# V1_1.net
KiCad netlist of a schematic drawn in Altium Designer
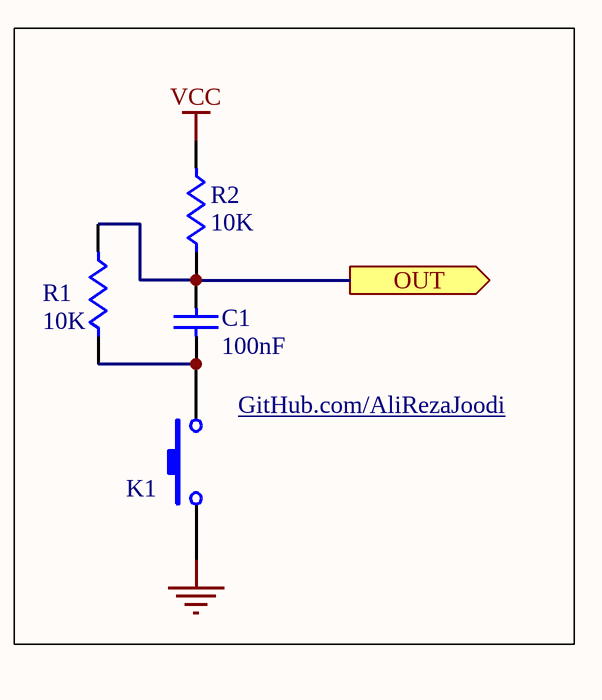
[diagram p0: V1.1.SchDoc]

(export (version "E")
  (design (tool "Eeschema 10.0.6"))
  (components
    (comp (ref "C1")
      (value "100nF")
      (footprint "CAPNTO2.54-3.56x2.03")
      (description "Capacitor")
      (fields (field (name "MANUFACTURER") "Generic Components") (field (name "PUBLISHER") "Altium Limited"))
      (libsource (lib "Miscellaneous Devices") (part "Cap"))
    )
    (comp (ref "K1")
      (value "SW-PB")
      (footprint "SPST-2_2")
      (description "Switch")
      (fields (field (name "MANUFACTURER") "Generic Components") (field (name "PUBLISHER") "Altium Limited"))
      (libsource (lib "Miscellaneous Devices") (part "SW-PB"))
    )
    (comp (ref "R1")
      (value "10K")
      (footprint "AXIAL-0.4")
      (description "Resistor")
      (fields (field (name "MANUFACTURER") "Generic Components") (field (name "PUBLISHER") "Altium Limited"))
      (libsource (lib "Miscellaneous Devices") (part "Res1"))
    )
    (comp (ref "R2")
      (value "10K")
      (footprint "AXIAL-0.4")
      (description "Resistor")
      (fields (field (name "MANUFACTURER") "Generic Components") (field (name "PUBLISHER") "Altium Limited"))
      (libsource (lib "Miscellaneous Devices") (part "Res1"))
    )
  )
  (nets
    (net (code "1") (name "/OUT") (class "Default")
      (node (ref "C1") (pin "1") (pinfunction "1_1") (pintype "passive"))
      (node (ref "R1") (pin "2") (pinfunction "2_2") (pintype "passive"))
      (node (ref "R2") (pin "1") (pinfunction "1_1") (pintype "passive"))
    )
    (net (code "2") (name "GND") (class "Default")
      (node (ref "K1") (pin "1") (pinfunction "1_1") (pintype "passive"))
    )
    (net (code "3") (name "Net-(C1-Pad2)") (class "Default")
      (node (ref "C1") (pin "2") (pinfunction "2_2") (pintype "passive"))
      (node (ref "K1") (pin "2") (pinfunction "2_2") (pintype "passive"))
      (node (ref "R1") (pin "1") (pinfunction "1_1") (pintype "passive"))
    )
    (net (code "4") (name "VCC") (class "Default")
      (node (ref "R2") (pin "2") (pinfunction "2_2") (pintype "passive"))
    )
  )
)
